# FS001.net
KiCad netlist of a schematic drawn in Altium Designer
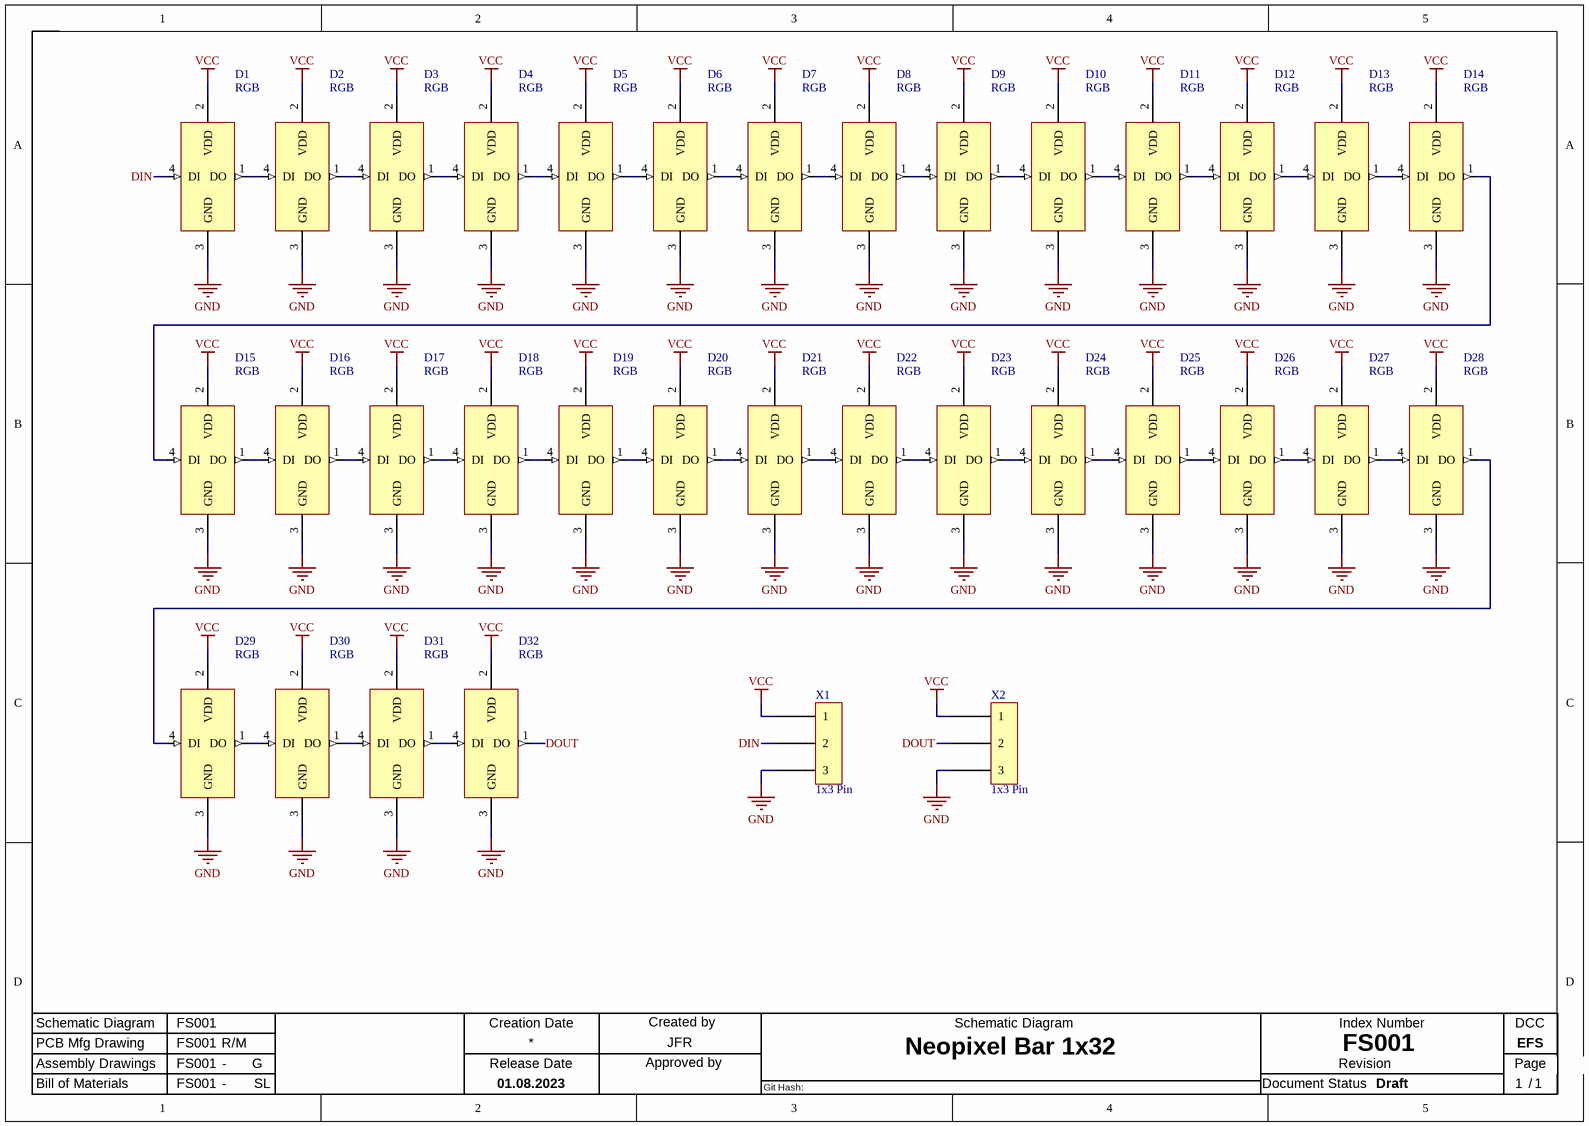
[diagram p0: FS001.SchDoc]

(export (version "E")
  (design (tool "Eeschema 10.0.6"))
  (components
    (comp (ref "D1")
      (value "RGB")
      (footprint "XINGLIGHT - XL1615RGBC-WS2812B")
      (description "Adressable RGB LED in 1615 enclosure")
      (fields
        (field (name "MANUFACTURER") "XINGLIGHT")
        (field (name "Comment") "XINGLIGHT - XL-1615RGBC-WS2812B")
      )
      (libsource (lib "Noris Automation GmbH") (part "Adressable LED 4-pin"))
    )
    (comp (ref "D2")
      (value "RGB")
      (footprint "XINGLIGHT - XL1615RGBC-WS2812B")
      (description "Adressable RGB LED in 1615 enclosure")
      (fields
        (field (name "MANUFACTURER") "XINGLIGHT")
        (field (name "Comment") "XINGLIGHT - XL-1615RGBC-WS2812B")
      )
      (libsource (lib "Noris Automation GmbH") (part "Adressable LED 4-pin"))
    )
    (comp (ref "D3")
      (value "RGB")
      (footprint "XINGLIGHT - XL1615RGBC-WS2812B")
      (description "Adressable RGB LED in 1615 enclosure")
      (fields
        (field (name "MANUFACTURER") "XINGLIGHT")
        (field (name "Comment") "XINGLIGHT - XL-1615RGBC-WS2812B")
      )
      (libsource (lib "Noris Automation GmbH") (part "Adressable LED 4-pin"))
    )
    (comp (ref "D4")
      (value "RGB")
      (footprint "XINGLIGHT - XL1615RGBC-WS2812B")
      (description "Adressable RGB LED in 1615 enclosure")
      (fields
        (field (name "MANUFACTURER") "XINGLIGHT")
        (field (name "Comment") "XINGLIGHT - XL-1615RGBC-WS2812B")
      )
      (libsource (lib "Noris Automation GmbH") (part "Adressable LED 4-pin"))
    )
    (comp (ref "D5")
      (value "RGB")
      (footprint "XINGLIGHT - XL1615RGBC-WS2812B")
      (description "Adressable RGB LED in 1615 enclosure")
      (fields
        (field (name "MANUFACTURER") "XINGLIGHT")
        (field (name "Comment") "XINGLIGHT - XL-1615RGBC-WS2812B")
      )
      (libsource (lib "Noris Automation GmbH") (part "Adressable LED 4-pin"))
    )
    (comp (ref "D6")
      (value "RGB")
      (footprint "XINGLIGHT - XL1615RGBC-WS2812B")
      (description "Adressable RGB LED in 1615 enclosure")
      (fields
        (field (name "MANUFACTURER") "XINGLIGHT")
        (field (name "Comment") "XINGLIGHT - XL-1615RGBC-WS2812B")
      )
      (libsource (lib "Noris Automation GmbH") (part "Adressable LED 4-pin"))
    )
    (comp (ref "D7")
      (value "RGB")
      (footprint "XINGLIGHT - XL1615RGBC-WS2812B")
      (description "Adressable RGB LED in 1615 enclosure")
      (fields
        (field (name "MANUFACTURER") "XINGLIGHT")
        (field (name "Comment") "XINGLIGHT - XL-1615RGBC-WS2812B")
      )
      (libsource (lib "Noris Automation GmbH") (part "Adressable LED 4-pin"))
    )
    (comp (ref "D8")
      (value "RGB")
      (footprint "XINGLIGHT - XL1615RGBC-WS2812B")
      (description "Adressable RGB LED in 1615 enclosure")
      (fields
        (field (name "MANUFACTURER") "XINGLIGHT")
        (field (name "Comment") "XINGLIGHT - XL-1615RGBC-WS2812B")
      )
      (libsource (lib "Noris Automation GmbH") (part "Adressable LED 4-pin"))
    )
    (comp (ref "D9")
      (value "RGB")
      (footprint "XINGLIGHT - XL1615RGBC-WS2812B")
      (description "Adressable RGB LED in 1615 enclosure")
      (fields
        (field (name "MANUFACTURER") "XINGLIGHT")
        (field (name "Comment") "XINGLIGHT - XL-1615RGBC-WS2812B")
      )
      (libsource (lib "Noris Automation GmbH") (part "Adressable LED 4-pin"))
    )
    (comp (ref "D10")
      (value "RGB")
      (footprint "XINGLIGHT - XL1615RGBC-WS2812B")
      (description "Adressable RGB LED in 1615 enclosure")
      (fields
        (field (name "MANUFACTURER") "XINGLIGHT")
        (field (name "Comment") "XINGLIGHT - XL-1615RGBC-WS2812B")
      )
      (libsource (lib "Noris Automation GmbH") (part "Adressable LED 4-pin"))
    )
    (comp (ref "D11")
      (value "RGB")
      (footprint "XINGLIGHT - XL1615RGBC-WS2812B")
      (description "Adressable RGB LED in 1615 enclosure")
      (fields
        (field (name "MANUFACTURER") "XINGLIGHT")
        (field (name "Comment") "XINGLIGHT - XL-1615RGBC-WS2812B")
      )
      (libsource (lib "Noris Automation GmbH") (part "Adressable LED 4-pin"))
    )
    (comp (ref "D12")
      (value "RGB")
      (footprint "XINGLIGHT - XL1615RGBC-WS2812B")
      (description "Adressable RGB LED in 1615 enclosure")
      (fields
        (field (name "MANUFACTURER") "XINGLIGHT")
        (field (name "Comment") "XINGLIGHT - XL-1615RGBC-WS2812B")
      )
      (libsource (lib "Noris Automation GmbH") (part "Adressable LED 4-pin"))
    )
    (comp (ref "D13")
      (value "RGB")
      (footprint "XINGLIGHT - XL1615RGBC-WS2812B")
      (description "Adressable RGB LED in 1615 enclosure")
      (fields
        (field (name "MANUFACTURER") "XINGLIGHT")
        (field (name "Comment") "XINGLIGHT - XL-1615RGBC-WS2812B")
      )
      (libsource (lib "Noris Automation GmbH") (part "Adressable LED 4-pin"))
    )
    (comp (ref "D14")
      (value "RGB")
      (footprint "XINGLIGHT - XL1615RGBC-WS2812B")
      (description "Adressable RGB LED in 1615 enclosure")
      (fields
        (field (name "MANUFACTURER") "XINGLIGHT")
        (field (name "Comment") "XINGLIGHT - XL-1615RGBC-WS2812B")
      )
      (libsource (lib "Noris Automation GmbH") (part "Adressable LED 4-pin"))
    )
    (comp (ref "D15")
      (value "RGB")
      (footprint "XINGLIGHT - XL1615RGBC-WS2812B")
      (description "Adressable RGB LED in 1615 enclosure")
      (fields
        (field (name "MANUFACTURER") "XINGLIGHT")
        (field (name "Comment") "XINGLIGHT - XL-1615RGBC-WS2812B")
      )
      (libsource (lib "Noris Automation GmbH") (part "Adressable LED 4-pin"))
    )
    (comp (ref "D16")
      (value "RGB")
      (footprint "XINGLIGHT - XL1615RGBC-WS2812B")
      (description "Adressable RGB LED in 1615 enclosure")
      (fields
        (field (name "MANUFACTURER") "XINGLIGHT")
        (field (name "Comment") "XINGLIGHT - XL-1615RGBC-WS2812B")
      )
      (libsource (lib "Noris Automation GmbH") (part "Adressable LED 4-pin"))
    )
    (comp (ref "D17")
      (value "RGB")
      (footprint "XINGLIGHT - XL1615RGBC-WS2812B")
      (description "Adressable RGB LED in 1615 enclosure")
      (fields
        (field (name "MANUFACTURER") "XINGLIGHT")
        (field (name "Comment") "XINGLIGHT - XL-1615RGBC-WS2812B")
      )
      (libsource (lib "Noris Automation GmbH") (part "Adressable LED 4-pin"))
    )
    (comp (ref "D18")
      (value "RGB")
      (footprint "XINGLIGHT - XL1615RGBC-WS2812B")
      (description "Adressable RGB LED in 1615 enclosure")
      (fields
        (field (name "MANUFACTURER") "XINGLIGHT")
        (field (name "Comment") "XINGLIGHT - XL-1615RGBC-WS2812B")
      )
      (libsource (lib "Noris Automation GmbH") (part "Adressable LED 4-pin"))
    )
    (comp (ref "D19")
      (value "RGB")
      (footprint "XINGLIGHT - XL1615RGBC-WS2812B")
      (description "Adressable RGB LED in 1615 enclosure")
      (fields
        (field (name "MANUFACTURER") "XINGLIGHT")
        (field (name "Comment") "XINGLIGHT - XL-1615RGBC-WS2812B")
      )
      (libsource (lib "Noris Automation GmbH") (part "Adressable LED 4-pin"))
    )
    (comp (ref "D20")
      (value "RGB")
      (footprint "XINGLIGHT - XL1615RGBC-WS2812B")
      (description "Adressable RGB LED in 1615 enclosure")
      (fields
        (field (name "MANUFACTURER") "XINGLIGHT")
        (field (name "Comment") "XINGLIGHT - XL-1615RGBC-WS2812B")
      )
      (libsource (lib "Noris Automation GmbH") (part "Adressable LED 4-pin"))
    )
    (comp (ref "D21")
      (value "RGB")
      (footprint "XINGLIGHT - XL1615RGBC-WS2812B")
      (description "Adressable RGB LED in 1615 enclosure")
      (fields
        (field (name "MANUFACTURER") "XINGLIGHT")
        (field (name "Comment") "XINGLIGHT - XL-1615RGBC-WS2812B")
      )
      (libsource (lib "Noris Automation GmbH") (part "Adressable LED 4-pin"))
    )
    (comp (ref "D22")
      (value "RGB")
      (footprint "XINGLIGHT - XL1615RGBC-WS2812B")
      (description "Adressable RGB LED in 1615 enclosure")
      (fields
        (field (name "MANUFACTURER") "XINGLIGHT")
        (field (name "Comment") "XINGLIGHT - XL-1615RGBC-WS2812B")
      )
      (libsource (lib "Noris Automation GmbH") (part "Adressable LED 4-pin"))
    )
    (comp (ref "D23")
      (value "RGB")
      (footprint "XINGLIGHT - XL1615RGBC-WS2812B")
      (description "Adressable RGB LED in 1615 enclosure")
      (fields
        (field (name "MANUFACTURER") "XINGLIGHT")
        (field (name "Comment") "XINGLIGHT - XL-1615RGBC-WS2812B")
      )
      (libsource (lib "Noris Automation GmbH") (part "Adressable LED 4-pin"))
    )
    (comp (ref "D24")
      (value "RGB")
      (footprint "XINGLIGHT - XL1615RGBC-WS2812B")
      (description "Adressable RGB LED in 1615 enclosure")
      (fields
        (field (name "MANUFACTURER") "XINGLIGHT")
        (field (name "Comment") "XINGLIGHT - XL-1615RGBC-WS2812B")
      )
      (libsource (lib "Noris Automation GmbH") (part "Adressable LED 4-pin"))
    )
    (comp (ref "D25")
      (value "RGB")
      (footprint "XINGLIGHT - XL1615RGBC-WS2812B")
      (description "Adressable RGB LED in 1615 enclosure")
      (fields
        (field (name "MANUFACTURER") "XINGLIGHT")
        (field (name "Comment") "XINGLIGHT - XL-1615RGBC-WS2812B")
      )
      (libsource (lib "Noris Automation GmbH") (part "Adressable LED 4-pin"))
    )
    (comp (ref "D26")
      (value "RGB")
      (footprint "XINGLIGHT - XL1615RGBC-WS2812B")
      (description "Adressable RGB LED in 1615 enclosure")
      (fields
        (field (name "MANUFACTURER") "XINGLIGHT")
        (field (name "Comment") "XINGLIGHT - XL-1615RGBC-WS2812B")
      )
      (libsource (lib "Noris Automation GmbH") (part "Adressable LED 4-pin"))
    )
    (comp (ref "D27")
      (value "RGB")
      (footprint "XINGLIGHT - XL1615RGBC-WS2812B")
      (description "Adressable RGB LED in 1615 enclosure")
      (fields
        (field (name "MANUFACTURER") "XINGLIGHT")
        (field (name "Comment") "XINGLIGHT - XL-1615RGBC-WS2812B")
      )
      (libsource (lib "Noris Automation GmbH") (part "Adressable LED 4-pin"))
    )
    (comp (ref "D28")
      (value "RGB")
      (footprint "XINGLIGHT - XL1615RGBC-WS2812B")
      (description "Adressable RGB LED in 1615 enclosure")
      (fields
        (field (name "MANUFACTURER") "XINGLIGHT")
        (field (name "Comment") "XINGLIGHT - XL-1615RGBC-WS2812B")
      )
      (libsource (lib "Noris Automation GmbH") (part "Adressable LED 4-pin"))
    )
    (comp (ref "D29")
      (value "RGB")
      (footprint "XINGLIGHT - XL1615RGBC-WS2812B")
      (description "Adressable RGB LED in 1615 enclosure")
      (fields
        (field (name "MANUFACTURER") "XINGLIGHT")
        (field (name "Comment") "XINGLIGHT - XL-1615RGBC-WS2812B")
      )
      (libsource (lib "Noris Automation GmbH") (part "Adressable LED 4-pin"))
    )
    (comp (ref "D30")
      (value "RGB")
      (footprint "XINGLIGHT - XL1615RGBC-WS2812B")
      (description "Adressable RGB LED in 1615 enclosure")
      (fields
        (field (name "MANUFACTURER") "XINGLIGHT")
        (field (name "Comment") "XINGLIGHT - XL-1615RGBC-WS2812B")
      )
      (libsource (lib "Noris Automation GmbH") (part "Adressable LED 4-pin"))
    )
    (comp (ref "D31")
      (value "RGB")
      (footprint "XINGLIGHT - XL1615RGBC-WS2812B")
      (description "Adressable RGB LED in 1615 enclosure")
      (fields
        (field (name "MANUFACTURER") "XINGLIGHT")
        (field (name "Comment") "XINGLIGHT - XL-1615RGBC-WS2812B")
      )
      (libsource (lib "Noris Automation GmbH") (part "Adressable LED 4-pin"))
    )
    (comp (ref "D32")
      (value "RGB")
      (footprint "XINGLIGHT - XL1615RGBC-WS2812B")
      (description "Adressable RGB LED in 1615 enclosure")
      (fields
        (field (name "MANUFACTURER") "XINGLIGHT")
        (field (name "Comment") "XINGLIGHT - XL-1615RGBC-WS2812B")
      )
      (libsource (lib "Noris Automation GmbH") (part "Adressable LED 4-pin"))
    )
    (comp (ref "X1")
      (value "1x3 Pin")
      (footprint "Pogo Pads 3-Pin")
      (description "Pads for contacting via spring loaded pogo contacts")
      (fields (field (name "MANUFACTURER") "NONE") (field (name "Comment") "Pogo Pads 3-Pin"))
      (libsource (lib "Noris Automation GmbH") (part "1x3 Pin Connector"))
    )
    (comp (ref "X2")
      (value "1x3 Pin")
      (footprint "Pogo Pads 3-Pin")
      (description "Pads for contacting via spring loaded pogo contacts")
      (fields (field (name "MANUFACTURER") "NONE") (field (name "Comment") "Pogo Pads 3-Pin"))
      (libsource (lib "Noris Automation GmbH") (part "1x3 Pin Connector"))
    )
  )
  (nets
    (net (code "1") (name "/DIN") (class "Default")
      (node (ref "D1") (pin "4") (pinfunction "DI_4") (pintype "input"))
      (node (ref "X1") (pin "2") (pinfunction "2_2") (pintype "passive"))
    )
    (net (code "2") (name "/DOUT") (class "Default")
      (node (ref "D32") (pin "1") (pinfunction "DO_1") (pintype "output"))
      (node (ref "X2") (pin "2") (pinfunction "2_2") (pintype "passive"))
    )
    (net (code "3") (name "GND") (class "Default")
      (node (ref "D1") (pin "3") (pinfunction "GND_3") (pintype "power_in"))
      (node (ref "D10") (pin "3") (pinfunction "GND_3") (pintype "power_in"))
      (node (ref "D11") (pin "3") (pinfunction "GND_3") (pintype "power_in"))
      (node (ref "D12") (pin "3") (pinfunction "GND_3") (pintype "power_in"))
      (node (ref "D13") (pin "3") (pinfunction "GND_3") (pintype "power_in"))
      (node (ref "D14") (pin "3") (pinfunction "GND_3") (pintype "power_in"))
      (node (ref "D15") (pin "3") (pinfunction "GND_3") (pintype "power_in"))
      (node (ref "D16") (pin "3") (pinfunction "GND_3") (pintype "power_in"))
      (node (ref "D17") (pin "3") (pinfunction "GND_3") (pintype "power_in"))
      (node (ref "D18") (pin "3") (pinfunction "GND_3") (pintype "power_in"))
      (node (ref "D19") (pin "3") (pinfunction "GND_3") (pintype "power_in"))
      (node (ref "D2") (pin "3") (pinfunction "GND_3") (pintype "power_in"))
      (node (ref "D20") (pin "3") (pinfunction "GND_3") (pintype "power_in"))
      (node (ref "D21") (pin "3") (pinfunction "GND_3") (pintype "power_in"))
      (node (ref "D22") (pin "3") (pinfunction "GND_3") (pintype "power_in"))
      (node (ref "D23") (pin "3") (pinfunction "GND_3") (pintype "power_in"))
      (node (ref "D24") (pin "3") (pinfunction "GND_3") (pintype "power_in"))
      (node (ref "D25") (pin "3") (pinfunction "GND_3") (pintype "power_in"))
      (node (ref "D26") (pin "3") (pinfunction "GND_3") (pintype "power_in"))
      (node (ref "D27") (pin "3") (pinfunction "GND_3") (pintype "power_in"))
      (node (ref "D28") (pin "3") (pinfunction "GND_3") (pintype "power_in"))
      (node (ref "D29") (pin "3") (pinfunction "GND_3") (pintype "power_in"))
      (node (ref "D3") (pin "3") (pinfunction "GND_3") (pintype "power_in"))
      (node (ref "D30") (pin "3") (pinfunction "GND_3") (pintype "power_in"))
      (node (ref "D31") (pin "3") (pinfunction "GND_3") (pintype "power_in"))
      (node (ref "D32") (pin "3") (pinfunction "GND_3") (pintype "power_in"))
      (node (ref "D4") (pin "3") (pinfunction "GND_3") (pintype "power_in"))
      (node (ref "D5") (pin "3") (pinfunction "GND_3") (pintype "power_in"))
      (node (ref "D6") (pin "3") (pinfunction "GND_3") (pintype "power_in"))
      (node (ref "D7") (pin "3") (pinfunction "GND_3") (pintype "power_in"))
      (node (ref "D8") (pin "3") (pinfunction "GND_3") (pintype "power_in"))
      (node (ref "D9") (pin "3") (pinfunction "GND_3") (pintype "power_in"))
      (node (ref "X1") (pin "3") (pinfunction "3_3") (pintype "passive"))
      (node (ref "X2") (pin "3") (pinfunction "3_3") (pintype "passive"))
    )
    (net (code "4") (name "Net-(D1-DO)") (class "Default")
      (node (ref "D1") (pin "1") (pinfunction "DO_1") (pintype "output"))
      (node (ref "D2") (pin "4") (pinfunction "DI_4") (pintype "input"))
    )
    (net (code "5") (name "Net-(D2-DO)") (class "Default")
      (node (ref "D2") (pin "1") (pinfunction "DO_1") (pintype "output"))
      (node (ref "D3") (pin "4") (pinfunction "DI_4") (pintype "input"))
    )
    (net (code "6") (name "Net-(D3-DO)") (class "Default")
      (node (ref "D3") (pin "1") (pinfunction "DO_1") (pintype "output"))
      (node (ref "D4") (pin "4") (pinfunction "DI_4") (pintype "input"))
    )
    (net (code "7") (name "Net-(D4-DO)") (class "Default")
      (node (ref "D4") (pin "1") (pinfunction "DO_1") (pintype "output"))
      (node (ref "D5") (pin "4") (pinfunction "DI_4") (pintype "input"))
    )
    (net (code "8") (name "Net-(D5-DO)") (class "Default")
      (node (ref "D5") (pin "1") (pinfunction "DO_1") (pintype "output"))
      (node (ref "D6") (pin "4") (pinfunction "DI_4") (pintype "input"))
    )
    (net (code "9") (name "Net-(D6-DO)") (class "Default")
      (node (ref "D6") (pin "1") (pinfunction "DO_1") (pintype "output"))
      (node (ref "D7") (pin "4") (pinfunction "DI_4") (pintype "input"))
    )
    (net (code "10") (name "Net-(D7-DO)") (class "Default")
      (node (ref "D7") (pin "1") (pinfunction "DO_1") (pintype "output"))
      (node (ref "D8") (pin "4") (pinfunction "DI_4") (pintype "input"))
    )
    (net (code "11") (name "Net-(D8-DO)") (class "Default")
      (node (ref "D8") (pin "1") (pinfunction "DO_1") (pintype "output"))
      (node (ref "D9") (pin "4") (pinfunction "DI_4") (pintype "input"))
    )
    (net (code "12") (name "Net-(D10-DI)") (class "Default")
      (node (ref "D10") (pin "4") (pinfunction "DI_4") (pintype "input"))
      (node (ref "D9") (pin "1") (pinfunction "DO_1") (pintype "output"))
    )
    (net (code "13") (name "Net-(D10-DO)") (class "Default")
      (node (ref "D10") (pin "1") (pinfunction "DO_1") (pintype "output"))
      (node (ref "D11") (pin "4") (pinfunction "DI_4") (pintype "input"))
    )
    (net (code "14") (name "Net-(D11-DO)") (class "Default")
      (node (ref "D11") (pin "1") (pinfunction "DO_1") (pintype "output"))
      (node (ref "D12") (pin "4") (pinfunction "DI_4") (pintype "input"))
    )
    (net (code "15") (name "Net-(D12-DO)") (class "Default")
      (node (ref "D12") (pin "1") (pinfunction "DO_1") (pintype "output"))
      (node (ref "D13") (pin "4") (pinfunction "DI_4") (pintype "input"))
    )
    (net (code "16") (name "Net-(D13-DO)") (class "Default")
      (node (ref "D13") (pin "1") (pinfunction "DO_1") (pintype "output"))
      (node (ref "D14") (pin "4") (pinfunction "DI_4") (pintype "input"))
    )
    (net (code "17") (name "Net-(D14-DO)") (class "Default")
      (node (ref "D14") (pin "1") (pinfunction "DO_1") (pintype "output"))
      (node (ref "D15") (pin "4") (pinfunction "DI_4") (pintype "input"))
    )
    (net (code "18") (name "Net-(D15-DO)") (class "Default")
      (node (ref "D15") (pin "1") (pinfunction "DO_1") (pintype "output"))
      (node (ref "D16") (pin "4") (pinfunction "DI_4") (pintype "input"))
    )
    (net (code "19") (name "Net-(D16-DO)") (class "Default")
      (node (ref "D16") (pin "1") (pinfunction "DO_1") (pintype "output"))
      (node (ref "D17") (pin "4") (pinfunction "DI_4") (pintype "input"))
    )
    (net (code "20") (name "Net-(D17-DO)") (class "Default")
      (node (ref "D17") (pin "1") (pinfunction "DO_1") (pintype "output"))
      (node (ref "D18") (pin "4") (pinfunction "DI_4") (pintype "input"))
    )
    (net (code "21") (name "Net-(D18-DO)") (class "Default")
      (node (ref "D18") (pin "1") (pinfunction "DO_1") (pintype "output"))
      (node (ref "D19") (pin "4") (pinfunction "DI_4") (pintype "input"))
    )
    (net (code "22") (name "Net-(D19-DO)") (class "Default")
      (node (ref "D19") (pin "1") (pinfunction "DO_1") (pintype "output"))
      (node (ref "D20") (pin "4") (pinfunction "DI_4") (pintype "input"))
    )
    (net (code "23") (name "Net-(D20-DO)") (class "Default")
      (node (ref "D20") (pin "1") (pinfunction "DO_1") (pintype "output"))
      (node (ref "D21") (pin "4") (pinfunction "DI_4") (pintype "input"))
    )
    (net (code "24") (name "Net-(D21-DO)") (class "Default")
      (node (ref "D21") (pin "1") (pinfunction "DO_1") (pintype "output"))
      (node (ref "D22") (pin "4") (pinfunction "DI_4") (pintype "input"))
    )
    (net (code "25") (name "Net-(D22-DO)") (class "Default")
      (node (ref "D22") (pin "1") (pinfunction "DO_1") (pintype "output"))
      (node (ref "D23") (pin "4") (pinfunction "DI_4") (pintype "input"))
    )
    (net (code "26") (name "Net-(D23-DO)") (class "Default")
      (node (ref "D23") (pin "1") (pinfunction "DO_1") (pintype "output"))
      (node (ref "D24") (pin "4") (pinfunction "DI_4") (pintype "input"))
    )
    (net (code "27") (name "Net-(D24-DO)") (class "Default")
      (node (ref "D24") (pin "1") (pinfunction "DO_1") (pintype "output"))
      (node (ref "D25") (pin "4") (pinfunction "DI_4") (pintype "input"))
    )
    (net (code "28") (name "Net-(D25-DO)") (class "Default")
      (node (ref "D25") (pin "1") (pinfunction "DO_1") (pintype "output"))
      (node (ref "D26") (pin "4") (pinfunction "DI_4") (pintype "input"))
    )
    (net (code "29") (name "Net-(D26-DO)") (class "Default")
      (node (ref "D26") (pin "1") (pinfunction "DO_1") (pintype "output"))
      (node (ref "D27") (pin "4") (pinfunction "DI_4") (pintype "input"))
    )
    (net (code "30") (name "Net-(D27-DO)") (class "Default")
      (node (ref "D27") (pin "1") (pinfunction "DO_1") (pintype "output"))
      (node (ref "D28") (pin "4") (pinfunction "DI_4") (pintype "input"))
    )
    (net (code "31") (name "Net-(D28-DO)") (class "Default")
      (node (ref "D28") (pin "1") (pinfunction "DO_1") (pintype "output"))
      (node (ref "D29") (pin "4") (pinfunction "DI_4") (pintype "input"))
    )
    (net (code "32") (name "Net-(D29-DO)") (class "Default")
      (node (ref "D29") (pin "1") (pinfunction "DO_1") (pintype "output"))
      (node (ref "D30") (pin "4") (pinfunction "DI_4") (pintype "input"))
    )
    (net (code "33") (name "Net-(D30-DO)") (class "Default")
      (node (ref "D30") (pin "1") (pinfunction "DO_1") (pintype "output"))
      (node (ref "D31") (pin "4") (pinfunction "DI_4") (pintype "input"))
    )
    (net (code "34") (name "Net-(D31-DO)") (class "Default")
      (node (ref "D31") (pin "1") (pinfunction "DO_1") (pintype "output"))
      (node (ref "D32") (pin "4") (pinfunction "DI_4") (pintype "input"))
    )
    (net (code "35") (name "VCC") (class "Default")
      (node (ref "D1") (pin "2") (pinfunction "VDD_2") (pintype "power_in"))
      (node (ref "D10") (pin "2") (pinfunction "VDD_2") (pintype "power_in"))
      (node (ref "D11") (pin "2") (pinfunction "VDD_2") (pintype "power_in"))
      (node (ref "D12") (pin "2") (pinfunction "VDD_2") (pintype "power_in"))
      (node (ref "D13") (pin "2") (pinfunction "VDD_2") (pintype "power_in"))
      (node (ref "D14") (pin "2") (pinfunction "VDD_2") (pintype "power_in"))
      (node (ref "D15") (pin "2") (pinfunction "VDD_2") (pintype "power_in"))
      (node (ref "D16") (pin "2") (pinfunction "VDD_2") (pintype "power_in"))
      (node (ref "D17") (pin "2") (pinfunction "VDD_2") (pintype "power_in"))
      (node (ref "D18") (pin "2") (pinfunction "VDD_2") (pintype "power_in"))
      (node (ref "D19") (pin "2") (pinfunction "VDD_2") (pintype "power_in"))
      (node (ref "D2") (pin "2") (pinfunction "VDD_2") (pintype "power_in"))
      (node (ref "D20") (pin "2") (pinfunction "VDD_2") (pintype "power_in"))
      (node (ref "D21") (pin "2") (pinfunction "VDD_2") (pintype "power_in"))
      (node (ref "D22") (pin "2") (pinfunction "VDD_2") (pintype "power_in"))
      (node (ref "D23") (pin "2") (pinfunction "VDD_2") (pintype "power_in"))
      (node (ref "D24") (pin "2") (pinfunction "VDD_2") (pintype "power_in"))
      (node (ref "D25") (pin "2") (pinfunction "VDD_2") (pintype "power_in"))
      (node (ref "D26") (pin "2") (pinfunction "VDD_2") (pintype "power_in"))
      (node (ref "D27") (pin "2") (pinfunction "VDD_2") (pintype "power_in"))
      (node (ref "D28") (pin "2") (pinfunction "VDD_2") (pintype "power_in"))
      (node (ref "D29") (pin "2") (pinfunction "VDD_2") (pintype "power_in"))
      (node (ref "D3") (pin "2") (pinfunction "VDD_2") (pintype "power_in"))
      (node (ref "D30") (pin "2") (pinfunction "VDD_2") (pintype "power_in"))
      (node (ref "D31") (pin "2") (pinfunction "VDD_2") (pintype "power_in"))
      (node (ref "D32") (pin "2") (pinfunction "VDD_2") (pintype "power_in"))
      (node (ref "D4") (pin "2") (pinfunction "VDD_2") (pintype "power_in"))
      (node (ref "D5") (pin "2") (pinfunction "VDD_2") (pintype "power_in"))
      (node (ref "D6") (pin "2") (pinfunction "VDD_2") (pintype "power_in"))
      (node (ref "D7") (pin "2") (pinfunction "VDD_2") (pintype "power_in"))
      (node (ref "D8") (pin "2") (pinfunction "VDD_2") (pintype "power_in"))
      (node (ref "D9") (pin "2") (pinfunction "VDD_2") (pintype "power_in"))
      (node (ref "X1") (pin "1") (pinfunction "1_1") (pintype "passive"))
      (node (ref "X2") (pin "1") (pinfunction "1_1") (pintype "passive"))
    )
  )
)
